# Physoon.net
KiCad netlist of a schematic drawn in EAGLE
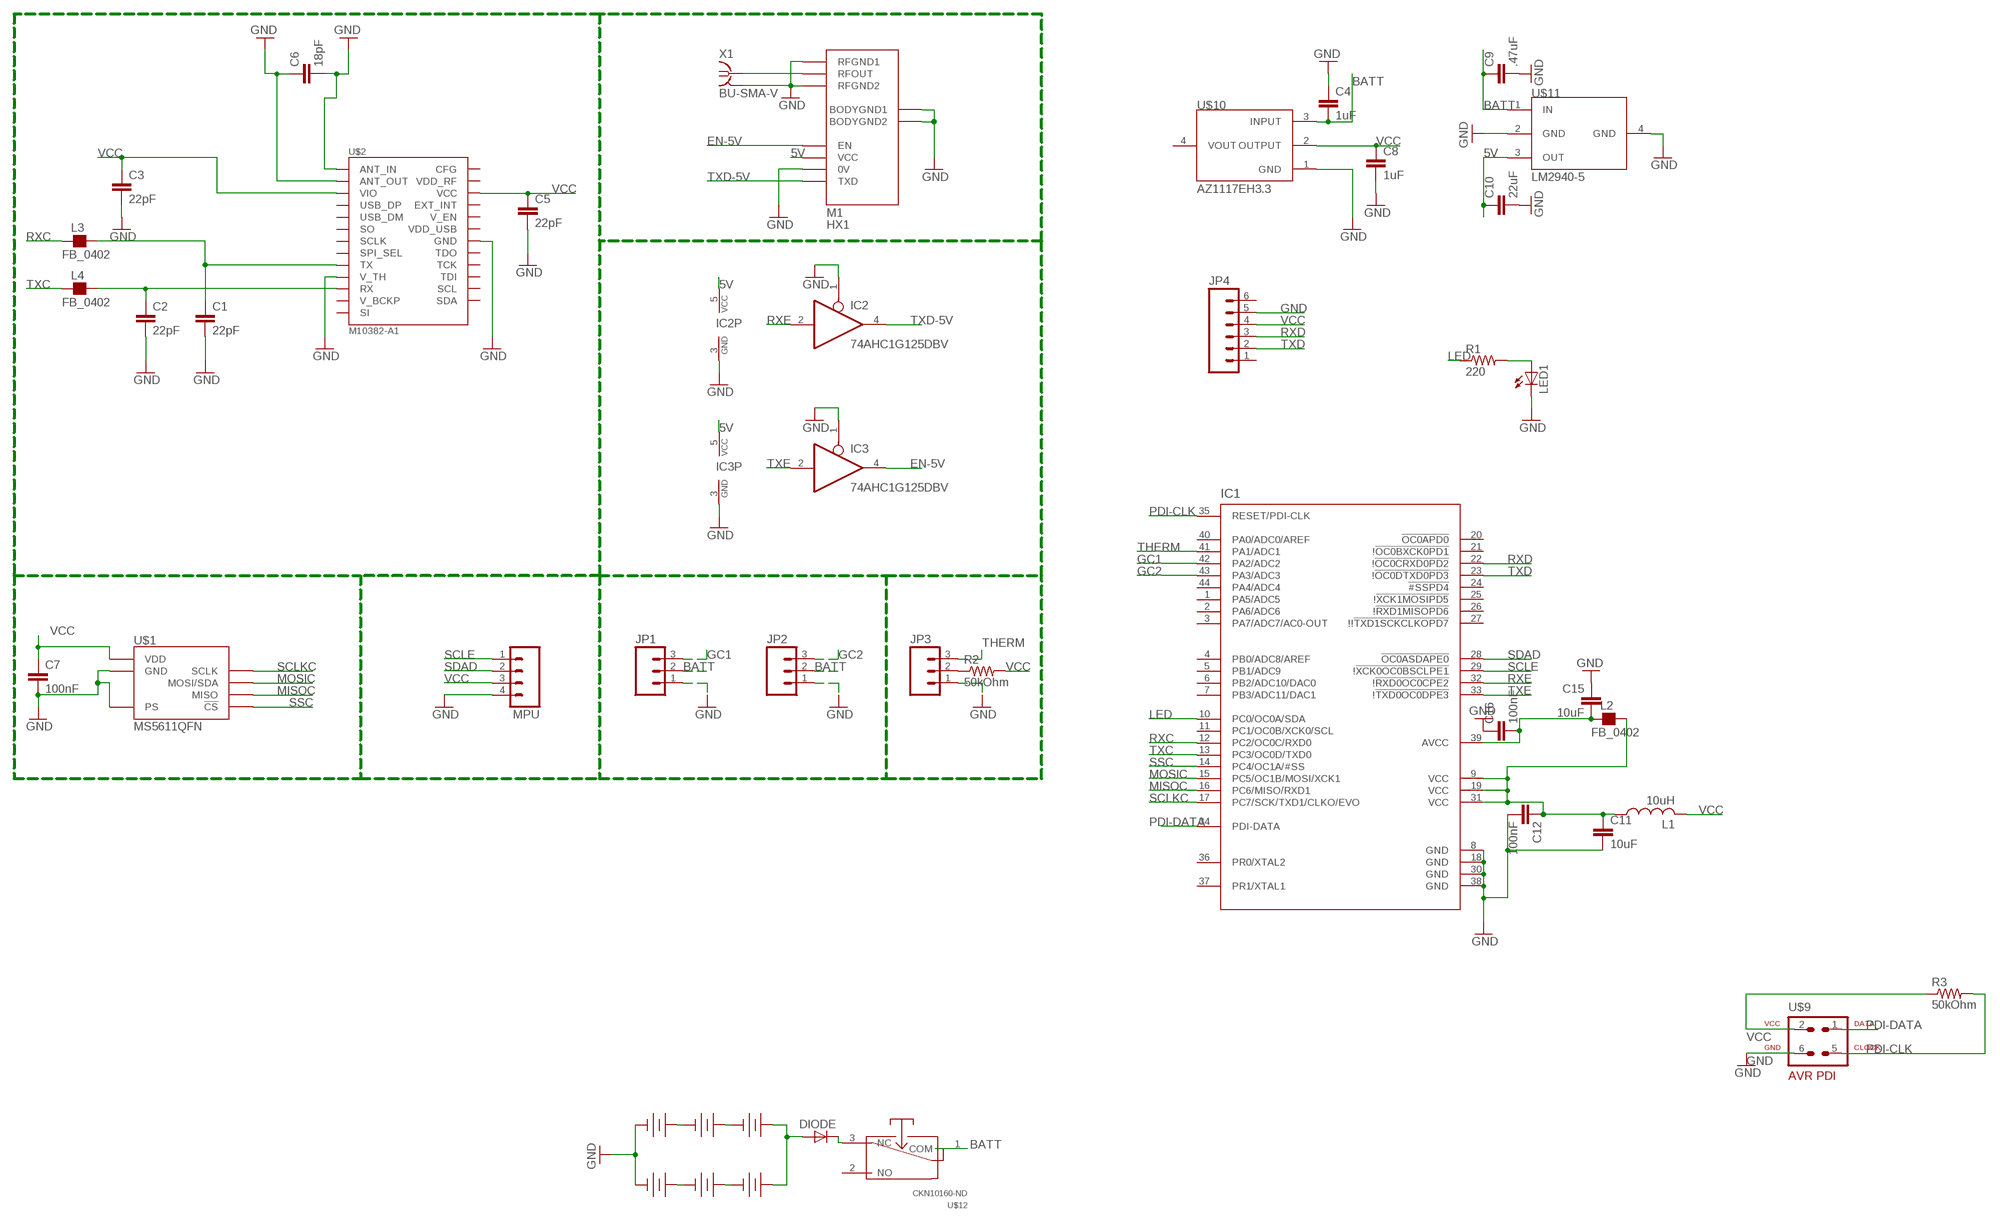
[diagram p0: schematic, sheet 1]

(export (version "E")
  (design (tool "Eeschema 10.0.6"))
  (components
    (comp (ref "C1")
      (value "22pF")
      (footprint "eagle-import:0805")
      (libsource (lib "eagle-import") (part "CAP0805"))
    )
    (comp (ref "C2")
      (value "22pF")
      (footprint "eagle-import:0805")
      (libsource (lib "eagle-import") (part "CAP0805"))
    )
    (comp (ref "C3")
      (value "22pF")
      (footprint "eagle-import:0805")
      (libsource (lib "eagle-import") (part "CAP0805"))
    )
    (comp (ref "C4")
      (value "1uF")
      (footprint "eagle-import:0603-CAP")
      (libsource (lib "eagle-import") (part "CAP0603-CAP"))
    )
    (comp (ref "C5")
      (value "22pF")
      (footprint "eagle-import:0805")
      (libsource (lib "eagle-import") (part "CAP0805"))
    )
    (comp (ref "C6")
      (value "18pF")
      (footprint "eagle-import:0805")
      (libsource (lib "eagle-import") (part "CAP0805"))
    )
    (comp (ref "C7")
      (value "100nF")
      (footprint "eagle-import:0805")
      (libsource (lib "eagle-import") (part "CAP0805"))
    )
    (comp (ref "C8")
      (value "1uF")
      (footprint "eagle-import:0603-CAP")
      (libsource (lib "eagle-import") (part "CAP0603-CAP"))
    )
    (comp (ref "C9")
      (value ".47uF")
      (footprint "eagle-import:0603-CAP")
      (libsource (lib "eagle-import") (part "CAP0603-CAP"))
    )
    (comp (ref "C10")
      (value "22uF")
      (footprint "eagle-import:0603-CAP")
      (libsource (lib "eagle-import") (part "CAP0603-CAP"))
    )
    (comp (ref "C11")
      (value "10uF")
      (footprint "eagle-import:0805")
      (libsource (lib "eagle-import") (part "CAP0805"))
    )
    (comp (ref "C12")
      (value "100nF")
      (footprint "eagle-import:0805")
      (libsource (lib "eagle-import") (part "CAP0805"))
    )
    (comp (ref "C15")
      (value "10uF")
      (footprint "eagle-import:0805")
      (libsource (lib "eagle-import") (part "CAP0805"))
    )
    (comp (ref "C16")
      (value "100nF")
      (footprint "eagle-import:0805")
      (libsource (lib "eagle-import") (part "CAP0805"))
    )
    (comp (ref "DIODE")
      (value "LILYPAD-WEARABLES_LED1206")
      (footprint "eagle-import:LILYPAD-WEARABLES_LED-1206")
      (libsource (lib "eagle-import") (part "LILYPAD-WEARABLES_LED1206"))
    )
    (comp (ref "IC1")
      (value "AT-XMEGA-XXA4-AU")
      (footprint "eagle-import:QFP80P1200X1200X120-44N")
      (libsource (lib "eagle-import") (part "AT-XMEGA-XXA4-AU"))
    )
    (comp (ref "IC2")
      (value "74AHC1G125DBV")
      (footprint "eagle-import:SOT23-5")
      (libsource (lib "eagle-import") (part "741G125DBVAHC"))
    )
    (comp (ref "IC3")
      (value "74AHC1G125DBV")
      (footprint "eagle-import:SOT23-5")
      (libsource (lib "eagle-import") (part "741G125DBVAHC"))
    )
    (comp (ref "JP1")
      (value "M03JST-PTH")
      (footprint "eagle-import:JST-3-PTH")
      (libsource (lib "eagle-import") (part "M03JST-PTH"))
    )
    (comp (ref "JP2")
      (value "M03JST-PTH")
      (footprint "eagle-import:JST-3-PTH")
      (libsource (lib "eagle-import") (part "M03JST-PTH"))
    )
    (comp (ref "JP3")
      (value "M03JST-PTH")
      (footprint "eagle-import:JST-3-PTH")
      (libsource (lib "eagle-import") (part "M03JST-PTH"))
    )
    (comp (ref "JP4")
      (value "M06POLAR")
      (footprint "eagle-import:MOLEX-1X6")
      (libsource (lib "eagle-import") (part "M06POLAR"))
    )
    (comp (ref "L1")
      (value "10uH")
      (footprint "eagle-import:L2012C")
      (libsource (lib "eagle-import") (part "L-USL2012C"))
    )
    (comp (ref "L2")
      (value "FB_0402")
      (footprint "eagle-import:L0402")
      (libsource (lib "eagle-import") (part "FB_0402"))
    )
    (comp (ref "L3")
      (value "FB_0402")
      (footprint "eagle-import:L0402")
      (libsource (lib "eagle-import") (part "FB_0402"))
    )
    (comp (ref "L4")
      (value "FB_0402")
      (footprint "eagle-import:L0402")
      (libsource (lib "eagle-import") (part "FB_0402"))
    )
    (comp (ref "LED1")
      (value "LEDCHIP-LED0603")
      (footprint "eagle-import:CHIP-LED0603")
      (libsource (lib "eagle-import") (part "LEDCHIP-LED0603"))
    )
    (comp (ref "M1")
      (value "HX1")
      (footprint "eagle-import:HX1")
      (libsource (lib "eagle-import") (part "HX1"))
    )
    (comp (ref "MPU")
      (value "M04")
      (footprint "eagle-import:04P")
      (libsource (lib "eagle-import") (part "M04"))
    )
    (comp (ref "R1")
      (value "220")
      (footprint "eagle-import:R0603")
      (libsource (lib "eagle-import") (part "R-US_R0603"))
    )
    (comp (ref "R2")
      (value "50kOhm")
      (footprint "eagle-import:0805")
      (libsource (lib "eagle-import") (part "RESISTOR0805-RES"))
    )
    (comp (ref "R3")
      (value "50kOhm")
      (footprint "eagle-import:0805")
      (libsource (lib "eagle-import") (part "RESISTOR0805-RES"))
    )
    (comp (ref "U$1")
      (value "MS5611QFN")
      (footprint "eagle-import:MS5611-01BA01")
      (libsource (lib "eagle-import") (part "MS5611QFN"))
    )
    (comp (ref "U$2")
      (value "M10382-A1")
      (footprint "eagle-import:M10382-A1")
      (libsource (lib "eagle-import") (part "M10382-A1"))
    )
    (comp (ref "U$3")
      (value "123_BATTERY_HOLDERCR-123-A")
      (footprint "eagle-import:CR-123-A_HOLDER")
      (libsource (lib "eagle-import") (part "123_BATTERY_HOLDERCR-123-A"))
    )
    (comp (ref "U$4")
      (value "123_BATTERY_HOLDERCR-123-A")
      (footprint "eagle-import:CR-123-A_HOLDER")
      (libsource (lib "eagle-import") (part "123_BATTERY_HOLDERCR-123-A"))
    )
    (comp (ref "U$5")
      (value "123_BATTERY_HOLDERCR-123-A")
      (footprint "eagle-import:CR-123-A_HOLDER")
      (libsource (lib "eagle-import") (part "123_BATTERY_HOLDERCR-123-A"))
    )
    (comp (ref "U$6")
      (value "123_BATTERY_HOLDERCR-123-A")
      (footprint "eagle-import:CR-123-A_HOLDER")
      (libsource (lib "eagle-import") (part "123_BATTERY_HOLDERCR-123-A"))
    )
    (comp (ref "U$7")
      (value "123_BATTERY_HOLDERCR-123-A")
      (footprint "eagle-import:CR-123-A_HOLDER")
      (libsource (lib "eagle-import") (part "123_BATTERY_HOLDERCR-123-A"))
    )
    (comp (ref "U$8")
      (value "123_BATTERY_HOLDERCR-123-A")
      (footprint "eagle-import:CR-123-A_HOLDER")
      (libsource (lib "eagle-import") (part "123_BATTERY_HOLDERCR-123-A"))
    )
    (comp (ref "U$9")
      (value "AVR-PDIVERT")
      (footprint "eagle-import:AVR-ISP-6")
      (libsource (lib "eagle-import") (part "AVR-PDIVERT"))
    )
    (comp (ref "U$10")
      (value "AZ1117EH3.3")
      (footprint "eagle-import:SOT-223")
      (libsource (lib "eagle-import") (part "AZ1117EH3.3"))
    )
    (comp (ref "U$11")
      (value "LM2940-5")
      (footprint "eagle-import:SOT-223")
      (libsource (lib "eagle-import") (part "LM2940-5"))
    )
    (comp (ref "U$12")
      (value "CKN10160-ND")
      (footprint "eagle-import:ZMCHFL3R")
      (libsource (lib "eagle-import") (part "CKN10160-ND"))
    )
    (comp (ref "X1")
      (value "BU-SMA-V")
      (footprint "eagle-import:BU-SMA-V")
      (libsource (lib "eagle-import") (part "BU-SMA-V"))
    )
  )
  (nets
    (net (code "1") (name "/5V") (class "Default")
      (node (ref "C10") (pin "1") (pinfunction "1_1") (pintype "passive"))
      (node (ref "IC2") (pin "5") (pinfunction "VCC_5") (pintype "power_in"))
      (node (ref "IC3") (pin "5") (pinfunction "VCC_5") (pintype "power_in"))
      (node (ref "M1") (pin "VCC") (pinfunction "VCC_VCC") (pintype "bidirectional"))
      (node (ref "U$11") (pin "3") (pinfunction "OUT_3") (pintype "bidirectional"))
    )
    (net (code "2") (name "/BATT") (class "Default")
      (node (ref "C4") (pin "2") (pinfunction "2_2") (pintype "passive"))
      (node (ref "C9") (pin "1") (pinfunction "1_1") (pintype "passive"))
      (node (ref "JP1") (pin "2") (pinfunction "2_2") (pintype "passive"))
      (node (ref "JP2") (pin "2") (pinfunction "2_2") (pintype "passive"))
      (node (ref "U$10") (pin "3") (pinfunction "INPUT_3") (pintype "bidirectional"))
      (node (ref "U$11") (pin "1") (pinfunction "IN_1") (pintype "bidirectional"))
      (node (ref "U$12") (pin "1") (pinfunction "COM_1") (pintype "bidirectional"))
    )
    (net (code "3") (name "/EN-5V") (class "Default")
      (node (ref "IC3") (pin "4") (pinfunction "O_4") (pintype "tri_state"))
      (node (ref "M1") (pin "EN") (pinfunction "EN_EN") (pintype "bidirectional"))
    )
    (net (code "4") (name "/GC1") (class "Default")
      (node (ref "IC1") (pin "42") (pinfunction "PA2/ADC2_42") (pintype "bidirectional"))
      (node (ref "JP1") (pin "3") (pinfunction "3_3") (pintype "passive"))
    )
    (net (code "5") (name "/GC2") (class "Default")
      (node (ref "IC1") (pin "43") (pinfunction "PA3/ADC3_43") (pintype "bidirectional"))
      (node (ref "JP2") (pin "3") (pinfunction "3_3") (pintype "passive"))
    )
    (net (code "6") (name "/LED") (class "Default")
      (node (ref "IC1") (pin "10") (pinfunction "PC0/OC0A/SDA_10") (pintype "bidirectional"))
      (node (ref "R1") (pin "1") (pinfunction "1_1") (pintype "passive"))
    )
    (net (code "7") (name "/MISOC") (class "Default")
      (node (ref "IC1") (pin "16") (pinfunction "PC6/MISO/RXD1_16") (pintype "bidirectional"))
      (node (ref "U$1") (pin "6") (pinfunction "MISO_6") (pintype "bidirectional"))
    )
    (net (code "8") (name "/MOSIC") (class "Default")
      (node (ref "IC1") (pin "15") (pinfunction "PC5/OC1B/MOSI/XCK1_15") (pintype "bidirectional"))
      (node (ref "U$1") (pin "7") (pinfunction "MOSI/SDA_7") (pintype "bidirectional"))
    )
    (net (code "9") (name "/PDI-CLK") (class "Default")
      (node (ref "IC1") (pin "35") (pinfunction "RESET/PDI-CLK_35") (pintype "input"))
      (node (ref "R3") (pin "2") (pinfunction "2_2") (pintype "passive"))
      (node (ref "U$9") (pin "5") (pinfunction "5_5") (pintype "passive"))
    )
    (net (code "10") (name "/PDI-DATA") (class "Default")
      (node (ref "IC1") (pin "34") (pinfunction "PDI-DATA_34") (pintype "bidirectional"))
      (node (ref "U$9") (pin "1") (pinfunction "1_1") (pintype "passive"))
    )
    (net (code "11") (name "/RXC") (class "Default")
      (node (ref "IC1") (pin "12") (pinfunction "PC2/OC0C/RXD0_12") (pintype "bidirectional"))
      (node (ref "L3") (pin "1") (pinfunction "1_1") (pintype "passive"))
    )
    (net (code "12") (name "/RXD") (class "Default")
      (node (ref "IC1") (pin "22") (pinfunction "~OC0CRXD0PD2_22") (pintype "bidirectional"))
      (node (ref "JP4") (pin "3") (pinfunction "3_3") (pintype "passive"))
    )
    (net (code "13") (name "/RXE") (class "Default")
      (node (ref "IC1") (pin "32") (pinfunction "~RXD0OC0CPE2_32") (pintype "bidirectional"))
      (node (ref "IC2") (pin "2") (pinfunction "I_2") (pintype "input"))
    )
    (net (code "14") (name "/SCLE") (class "Default")
      (node (ref "IC1") (pin "29") (pinfunction "~XCK0OC0BSCLPE1_29") (pintype "bidirectional"))
      (node (ref "MPU") (pin "1") (pinfunction "1_1") (pintype "passive"))
    )
    (net (code "15") (name "/SCLKC") (class "Default")
      (node (ref "IC1") (pin "17") (pinfunction "PC7/SCK/TXD1/CLKO/EVO_17") (pintype "bidirectional"))
      (node (ref "U$1") (pin "8") (pinfunction "SCLK_8") (pintype "bidirectional"))
    )
    (net (code "16") (name "/SDAD") (class "Default")
      (node (ref "IC1") (pin "28") (pinfunction "~{OC0ASDAPE0}_28") (pintype "bidirectional"))
      (node (ref "MPU") (pin "2") (pinfunction "2_2") (pintype "passive"))
    )
    (net (code "17") (name "/SSC") (class "Default")
      (node (ref "IC1") (pin "14") (pinfunction "PC4/OC1A/#SS_14") (pintype "bidirectional"))
      (node (ref "U$1") (pin "4") (pinfunction "~{CS}_4") (pintype "bidirectional"))
      (node (ref "U$1") (pin "5") (pinfunction "~{CS}_5") (pintype "bidirectional"))
    )
    (net (code "18") (name "/THERM") (class "Default")
      (node (ref "IC1") (pin "41") (pinfunction "PA1/ADC1_41") (pintype "bidirectional"))
      (node (ref "JP3") (pin "3") (pinfunction "3_3") (pintype "passive"))
    )
    (net (code "19") (name "/TXC") (class "Default")
      (node (ref "IC1") (pin "13") (pinfunction "PC3/OC0D/TXD0_13") (pintype "bidirectional"))
      (node (ref "L4") (pin "1") (pinfunction "1_1") (pintype "passive"))
    )
    (net (code "20") (name "/TXD") (class "Default")
      (node (ref "IC1") (pin "23") (pinfunction "~OC0DTXD0PD3_23") (pintype "bidirectional"))
      (node (ref "JP4") (pin "2") (pinfunction "2_2") (pintype "passive"))
    )
    (net (code "21") (name "/TXD-5V") (class "Default")
      (node (ref "IC2") (pin "4") (pinfunction "O_4") (pintype "tri_state"))
      (node (ref "M1") (pin "TXD") (pinfunction "TXD_TXD") (pintype "bidirectional"))
    )
    (net (code "22") (name "/TXE") (class "Default")
      (node (ref "IC1") (pin "33") (pinfunction "~TXD0OC0DPE3_33") (pintype "bidirectional"))
      (node (ref "IC3") (pin "2") (pinfunction "I_2") (pintype "input"))
    )
    (net (code "23") (name "/VCC") (class "Default")
      (node (ref "C3") (pin "1") (pinfunction "1_1") (pintype "passive"))
      (node (ref "C5") (pin "1") (pinfunction "1_1") (pintype "passive"))
      (node (ref "C7") (pin "1") (pinfunction "1_1") (pintype "passive"))
      (node (ref "C8") (pin "1") (pinfunction "1_1") (pintype "passive"))
      (node (ref "JP4") (pin "4") (pinfunction "4_4") (pintype "passive"))
      (node (ref "L1") (pin "2") (pinfunction "2_2") (pintype "passive"))
      (node (ref "MPU") (pin "3") (pinfunction "3_3") (pintype "passive"))
      (node (ref "R2") (pin "2") (pinfunction "2_2") (pintype "passive"))
      (node (ref "R3") (pin "1") (pinfunction "1_1") (pintype "passive"))
      (node (ref "U$1") (pin "1") (pinfunction "VDD_1") (pintype "bidirectional"))
      (node (ref "U$10") (pin "2") (pinfunction "OUTPUT_2") (pintype "bidirectional"))
      (node (ref "U$2") (pin "27") (pinfunction "VCC_27") (pintype "bidirectional"))
      (node (ref "U$2") (pin "5") (pinfunction "VIO_5") (pintype "bidirectional"))
      (node (ref "U$9") (pin "2") (pinfunction "2_2") (pintype "passive"))
    )
    (net (code "24") (name "GND") (class "Default")
      (node (ref "C1") (pin "2") (pinfunction "2_2") (pintype "passive"))
      (node (ref "C10") (pin "2") (pinfunction "2_2") (pintype "passive"))
      (node (ref "C11") (pin "2") (pinfunction "2_2") (pintype "passive"))
      (node (ref "C12") (pin "2") (pinfunction "2_2") (pintype "passive"))
      (node (ref "C15") (pin "1") (pinfunction "1_1") (pintype "passive"))
      (node (ref "C16") (pin "1") (pinfunction "1_1") (pintype "passive"))
      (node (ref "C2") (pin "2") (pinfunction "2_2") (pintype "passive"))
      (node (ref "C3") (pin "2") (pinfunction "2_2") (pintype "passive"))
      (node (ref "C4") (pin "1") (pinfunction "1_1") (pintype "passive"))
      (node (ref "C5") (pin "2") (pinfunction "2_2") (pintype "passive"))
      (node (ref "C6") (pin "1") (pinfunction "1_1") (pintype "passive"))
      (node (ref "C6") (pin "2") (pinfunction "2_2") (pintype "passive"))
      (node (ref "C7") (pin "2") (pinfunction "2_2") (pintype "passive"))
      (node (ref "C8") (pin "2") (pinfunction "2_2") (pintype "passive"))
      (node (ref "C9") (pin "2") (pinfunction "2_2") (pintype "passive"))
      (node (ref "IC1") (pin "18") (pinfunction "GND_18") (pintype "power_in"))
      (node (ref "IC1") (pin "30") (pinfunction "GND_30") (pintype "power_in"))
      (node (ref "IC1") (pin "38") (pinfunction "GND_38") (pintype "power_in"))
      (node (ref "IC1") (pin "8") (pinfunction "GND_8") (pintype "power_in"))
      (node (ref "IC2") (pin "1") (pinfunction "OE_1") (pintype "input"))
      (node (ref "IC2") (pin "3") (pinfunction "GND_3") (pintype "power_in"))
      (node (ref "IC3") (pin "1") (pinfunction "OE_1") (pintype "input"))
      (node (ref "IC3") (pin "3") (pinfunction "GND_3") (pintype "power_in"))
      (node (ref "JP1") (pin "1") (pinfunction "1_1") (pintype "passive"))
      (node (ref "JP2") (pin "1") (pinfunction "1_1") (pintype "passive"))
      (node (ref "JP3") (pin "1") (pinfunction "1_1") (pintype "passive"))
      (node (ref "JP4") (pin "5") (pinfunction "5_5") (pintype "passive"))
      (node (ref "LED1") (pin "C") (pinfunction "C_C") (pintype "passive"))
      (node (ref "M1") (pin "0V") (pinfunction "0V_0V") (pintype "bidirectional"))
      (node (ref "M1") (pin "BODYGND1") (pinfunction "BODYGND1_BODYGND1") (pintype "bidirectional"))
      (node (ref "M1") (pin "BODYGND2") (pinfunction "BODYGND2_BODYGND2") (pintype "bidirectional"))
      (node (ref "M1") (pin "RFGND1") (pinfunction "RFGND1_RFGND1") (pintype "bidirectional"))
      (node (ref "M1") (pin "RFGND2") (pinfunction "RFGND2_RFGND2") (pintype "bidirectional"))
      (node (ref "MPU") (pin "4") (pinfunction "4_4") (pintype "passive"))
      (node (ref "U$1") (pin "2") (pinfunction "PS_2") (pintype "bidirectional"))
      (node (ref "U$1") (pin "3") (pinfunction "GND_3") (pintype "bidirectional"))
      (node (ref "U$10") (pin "1") (pinfunction "GND_1") (pintype "bidirectional"))
      (node (ref "U$11") (pin "2") (pinfunction "GND_2") (pintype "bidirectional"))
      (node (ref "U$11") (pin "4") (pinfunction "GND_4") (pintype "bidirectional"))
      (node (ref "U$2") (pin "1") (pinfunction "ANT_IN_1") (pintype "bidirectional"))
      (node (ref "U$2") (pin "12") (pinfunction "V_TH_12") (pintype "bidirectional"))
      (node (ref "U$2") (pin "14") (pinfunction "GND_14") (pintype "bidirectional"))
      (node (ref "U$2") (pin "17") (pinfunction "GND_17") (pintype "bidirectional"))
      (node (ref "U$2") (pin "2") (pinfunction "GND_2") (pintype "bidirectional"))
      (node (ref "U$2") (pin "21") (pinfunction "GND_21") (pintype "bidirectional"))
      (node (ref "U$2") (pin "24") (pinfunction "GND_24") (pintype "bidirectional"))
      (node (ref "U$2") (pin "26") (pinfunction "GND_26") (pintype "bidirectional"))
      (node (ref "U$2") (pin "28") (pinfunction "GND_28") (pintype "bidirectional"))
      (node (ref "U$2") (pin "3") (pinfunction "ANT_OUT_3") (pintype "bidirectional"))
      (node (ref "U$2") (pin "33") (pinfunction "GND_33") (pintype "bidirectional"))
      (node (ref "U$2") (pin "34") (pinfunction "GND_34") (pintype "bidirectional"))
      (node (ref "U$2") (pin "35") (pinfunction "GND_35") (pintype "bidirectional"))
      (node (ref "U$2") (pin "36") (pinfunction "GND_36") (pintype "bidirectional"))
      (node (ref "U$2") (pin "4") (pinfunction "GND_4") (pintype "bidirectional"))
      (node (ref "U$3") (pin "-") (pinfunction "-_-") (pintype "bidirectional"))
      (node (ref "U$6") (pin "-") (pinfunction "-_-") (pintype "bidirectional"))
      (node (ref "U$9") (pin "6") (pinfunction "6_6") (pintype "passive"))
      (node (ref "X1") (pin "2") (pinfunction "GND_2") (pintype "power_in"))
    )
    (net (code "25") (name "Net-(C11-Pad1)") (class "Default")
      (node (ref "C11") (pin "1") (pinfunction "1_1") (pintype "passive"))
      (node (ref "C12") (pin "1") (pinfunction "1_1") (pintype "passive"))
      (node (ref "IC1") (pin "19") (pinfunction "VCC_19") (pintype "power_in"))
      (node (ref "IC1") (pin "31") (pinfunction "VCC_31") (pintype "power_in"))
      (node (ref "IC1") (pin "9") (pinfunction "VCC_9") (pintype "power_in"))
      (node (ref "L1") (pin "1") (pinfunction "1_1") (pintype "passive"))
      (node (ref "L2") (pin "2") (pinfunction "2_2") (pintype "passive"))
    )
    (net (code "26") (name "Net-(DIODE-PadA)") (class "Default")
      (node (ref "DIODE") (pin "A") (pinfunction "A_A") (pintype "passive"))
      (node (ref "U$5") (pin "+") (pinfunction "+_+") (pintype "bidirectional"))
      (node (ref "U$8") (pin "+") (pinfunction "+_+") (pintype "bidirectional"))
    )
    (net (code "27") (name "Net-(IC1-AVCC)") (class "Default")
      (node (ref "C15") (pin "2") (pinfunction "2_2") (pintype "passive"))
      (node (ref "C16") (pin "2") (pinfunction "2_2") (pintype "passive"))
      (node (ref "IC1") (pin "39") (pinfunction "AVCC_39") (pintype "power_in"))
      (node (ref "L2") (pin "1") (pinfunction "1_1") (pintype "passive"))
    )
    (net (code "28") (name "Net-(JP3-Pad2)") (class "Default")
      (node (ref "JP3") (pin "2") (pinfunction "2_2") (pintype "passive"))
      (node (ref "R2") (pin "1") (pinfunction "1_1") (pintype "passive"))
    )
    (net (code "29") (name "Net-(LED1-PadA)") (class "Default")
      (node (ref "LED1") (pin "A") (pinfunction "A_A") (pintype "passive"))
      (node (ref "R1") (pin "2") (pinfunction "2_2") (pintype "passive"))
    )
    (net (code "30") (name "Net-(M1-PadRFOUT)") (class "Default")
      (node (ref "M1") (pin "RFOUT") (pinfunction "RFOUT_RFOUT") (pintype "bidirectional"))
      (node (ref "X1") (pin "1") (pinfunction "1_1") (pintype "passive"))
    )
    (net (code "31") (name "Net-(U$2-RX)") (class "Default")
      (node (ref "C2") (pin "1") (pinfunction "1_1") (pintype "passive"))
      (node (ref "L4") (pin "2") (pinfunction "2_2") (pintype "passive"))
      (node (ref "U$2") (pin "13") (pinfunction "RX_13") (pintype "bidirectional"))
    )
    (net (code "32") (name "Net-(U$2-TX)") (class "Default")
      (node (ref "C1") (pin "1") (pinfunction "1_1") (pintype "passive"))
      (node (ref "L3") (pin "2") (pinfunction "2_2") (pintype "passive"))
      (node (ref "U$2") (pin "11") (pinfunction "TX_11") (pintype "bidirectional"))
    )
    (net (code "33") (name "Net-(U$3-Pad+)") (class "Default")
      (node (ref "U$3") (pin "+") (pinfunction "+_+") (pintype "bidirectional"))
      (node (ref "U$4") (pin "-") (pinfunction "-_-") (pintype "bidirectional"))
    )
    (net (code "34") (name "Net-(U$4-Pad+)") (class "Default")
      (node (ref "U$4") (pin "+") (pinfunction "+_+") (pintype "bidirectional"))
      (node (ref "U$5") (pin "-") (pinfunction "-_-") (pintype "bidirectional"))
    )
    (net (code "35") (name "Net-(U$6-Pad+)") (class "Default")
      (node (ref "U$6") (pin "+") (pinfunction "+_+") (pintype "bidirectional"))
      (node (ref "U$7") (pin "-") (pinfunction "-_-") (pintype "bidirectional"))
    )
    (net (code "36") (name "Net-(U$7-Pad+)") (class "Default")
      (node (ref "U$7") (pin "+") (pinfunction "+_+") (pintype "bidirectional"))
      (node (ref "U$8") (pin "-") (pinfunction "-_-") (pintype "bidirectional"))
    )
    (net (code "37") (name "Net-(U$12-NC)") (class "Default")
      (node (ref "DIODE") (pin "C") (pinfunction "C_C") (pintype "passive"))
      (node (ref "U$12") (pin "3") (pinfunction "NC_3") (pintype "bidirectional"))
    )
    (net (code "38") (name "unconnected-(IC1-PA0{slash}ADC0{slash}AREF-Pad40)") (class "Default")
      (node (ref "IC1") (pin "40") (pinfunction "PA0/ADC0/AREF_40") (pintype "bidirectional"))
    )
    (net (code "39") (name "unconnected-(IC1-PA4{slash}ADC4-Pad44)") (class "Default")
      (node (ref "IC1") (pin "44") (pinfunction "PA4/ADC4_44") (pintype "bidirectional"))
    )
    (net (code "40") (name "unconnected-(IC1-PA5{slash}ADC5-Pad1)") (class "Default")
      (node (ref "IC1") (pin "1") (pinfunction "PA5/ADC5_1") (pintype "bidirectional"))
    )
    (net (code "41") (name "unconnected-(IC1-PA6{slash}ADC6-Pad2)") (class "Default")
      (node (ref "IC1") (pin "2") (pinfunction "PA6/ADC6_2") (pintype "bidirectional"))
    )
    (net (code "42") (name "unconnected-(IC1-PA7{slash}ADC7{slash}AC0-OUT-Pad3)") (class "Default")
      (node (ref "IC1") (pin "3") (pinfunction "PA7/ADC7/AC0-OUT_3") (pintype "bidirectional"))
    )
    (net (code "43") (name "unconnected-(IC1-PB0{slash}ADC8{slash}AREF-Pad4)") (class "Default")
      (node (ref "IC1") (pin "4") (pinfunction "PB0/ADC8/AREF_4") (pintype "bidirectional"))
    )
    (net (code "44") (name "unconnected-(IC1-PB1{slash}ADC9-Pad5)") (class "Default")
      (node (ref "IC1") (pin "5") (pinfunction "PB1/ADC9_5") (pintype "bidirectional"))
    )
    (net (code "45") (name "unconnected-(IC1-PB2{slash}ADC10{slash}DAC0-Pad6)") (class "Default")
      (node (ref "IC1") (pin "6") (pinfunction "PB2/ADC10/DAC0_6") (pintype "bidirectional"))
    )
    (net (code "46") (name "unconnected-(IC1-PB3{slash}ADC11{slash}DAC1-Pad7)") (class "Default")
      (node (ref "IC1") (pin "7") (pinfunction "PB3/ADC11/DAC1_7") (pintype "bidirectional"))
    )
    (net (code "47") (name "unconnected-(IC1-PC1{slash}OC0B{slash}XCK0{slash}SCL-Pad11)") (class "Default")
      (node (ref "IC1") (pin "11") (pinfunction "PC1/OC0B/XCK0/SCL_11") (pintype "bidirectional"))
    )
    (net (code "48") (name "unconnected-(IC1-PR0{slash}XTAL2-Pad36)") (class "Default")
      (node (ref "IC1") (pin "36") (pinfunction "PR0/XTAL2_36") (pintype "bidirectional"))
    )
    (net (code "49") (name "unconnected-(IC1-PR1{slash}XTAL1-Pad37)") (class "Default")
      (node (ref "IC1") (pin "37") (pinfunction "PR1/XTAL1_37") (pintype "bidirectional"))
    )
    (net (code "50") (name "unconnected-(IC1-~OC0BXCK0PD1-Pad21)") (class "Default")
      (node (ref "IC1") (pin "21") (pinfunction "~OC0BXCK0PD1_21") (pintype "bidirectional"))
    )
    (net (code "51") (name "unconnected-(IC1-~RXD1MISOPD6-Pad26)") (class "Default")
      (node (ref "IC1") (pin "26") (pinfunction "~RXD1MISOPD6_26") (pintype "bidirectional"))
    )
    (net (code "52") (name "unconnected-(IC1-~XCK1MOSIPD5-Pad25)") (class "Default")
      (node (ref "IC1") (pin "25") (pinfunction "~XCK1MOSIPD5_25") (pintype "bidirectional"))
    )
    (net (code "53") (name "unconnected-(IC1-~{#SSPD4}-Pad24)") (class "Default")
      (node (ref "IC1") (pin "24") (pinfunction "~{#SSPD4}_24") (pintype "bidirectional"))
    )
    (net (code "54") (name "unconnected-(IC1-~{OC0APD0}-Pad20)") (class "Default")
      (node (ref "IC1") (pin "20") (pinfunction "~{OC0APD0}_20") (pintype "bidirectional"))
    )
    (net (code "55") (name "unconnected-(IC1-~~{TXD1SCKCLKOPD7}-Pad27)") (class "Default")
      (node (ref "IC1") (pin "27") (pinfunction "~~{TXD1SCKCLKOPD7}_27") (pintype "bidirectional"))
    )
    (net (code "56") (name "unconnected-(JP4-Pad1)") (class "Default")
      (node (ref "JP4") (pin "1") (pinfunction "1_1") (pintype "passive"))
    )
    (net (code "57") (name "unconnected-(JP4-Pad6)") (class "Default")
      (node (ref "JP4") (pin "6") (pinfunction "6_6") (pintype "passive"))
    )
    (net (code "58") (name "unconnected-(U$2-CFG-Pad31)") (class "Default")
      (node (ref "U$2") (pin "31") (pinfunction "CFG_31") (pintype "bidirectional"))
    )
    (net (code "59") (name "unconnected-(U$2-EXT_INT-Pad29)") (class "Default")
      (node (ref "U$2") (pin "29") (pinfunction "EXT_INT_29") (pintype "bidirectional"))
    )
    (net (code "60") (name "unconnected-(U$2-SCL-Pad19)") (class "Default")
      (node (ref "U$2") (pin "19") (pinfunction "SCL_19") (pintype "bidirectional"))
    )
    (net (code "61") (name "unconnected-(U$2-SCLK-Pad9)") (class "Default")
      (node (ref "U$2") (pin "9") (pinfunction "SCLK_9") (pintype "bidirectional"))
    )
    (net (code "62") (name "unconnected-(U$2-SDA-Pad18)") (class "Default")
      (node (ref "U$2") (pin "18") (pinfunction "SDA_18") (pintype "bidirectional"))
    )
    (net (code "63") (name "unconnected-(U$2-SI-Pad16)") (class "Default")
      (node (ref "U$2") (pin "16") (pinfunction "SI_16") (pintype "bidirectional"))
    )
    (net (code "64") (name "unconnected-(U$2-SO-Pad8)") (class "Default")
      (node (ref "U$2") (pin "8") (pinfunction "SO_8") (pintype "bidirectional"))
    )
    (net (code "65") (name "unconnected-(U$2-SPI_SEL-Pad10)") (class "Default")
      (node (ref "U$2") (pin "10") (pinfunction "SPI_SEL_10") (pintype "bidirectional"))
    )
    (net (code "66") (name "unconnected-(U$2-TCK-Pad22)") (class "Default")
      (node (ref "U$2") (pin "22") (pinfunction "TCK_22") (pintype "bidirectional"))
    )
    (net (code "67") (name "unconnected-(U$2-TDI-Pad20)") (class "Default")
      (node (ref "U$2") (pin "20") (pinfunction "TDI_20") (pintype "bidirectional"))
    )
    (net (code "68") (name "unconnected-(U$2-TDO-Pad23)") (class "Default")
      (node (ref "U$2") (pin "23") (pinfunction "TDO_23") (pintype "bidirectional"))
    )
    (net (code "69") (name "unconnected-(U$2-USB_DM-Pad7)") (class "Default")
      (node (ref "U$2") (pin "7") (pinfunction "USB_DM_7") (pintype "bidirectional"))
    )
    (net (code "70") (name "unconnected-(U$2-USB_DP-Pad6)") (class "Default")
      (node (ref "U$2") (pin "6") (pinfunction "USB_DP_6") (pintype "bidirectional"))
    )
    (net (code "71") (name "unconnected-(U$2-VDD_RF-Pad25)") (class "Default")
      (node (ref "U$2") (pin "25") (pinfunction "VDD_RF_25") (pintype "bidirectional"))
    )
    (net (code "72") (name "unconnected-(U$2-VDD_USB-Pad32)") (class "Default")
      (node (ref "U$2") (pin "32") (pinfunction "VDD_USB_32") (pintype "bidirectional"))
    )
    (net (code "73") (name "unconnected-(U$2-V_BCKP-Pad15)") (class "Default")
      (node (ref "U$2") (pin "15") (pinfunction "V_BCKP_15") (pintype "bidirectional"))
    )
    (net (code "74") (name "unconnected-(U$2-V_EN-Pad30)") (class "Default")
      (node (ref "U$2") (pin "30") (pinfunction "V_EN_30") (pintype "bidirectional"))
    )
    (net (code "75") (name "unconnected-(U$10-VOUT-Pad4)") (class "Default")
      (node (ref "U$10") (pin "4") (pinfunction "VOUT_4") (pintype "bidirectional"))
    )
    (net (code "76") (name "unconnected-(U$12-NO-Pad2)") (class "Default")
      (node (ref "U$12") (pin "2") (pinfunction "NO_2") (pintype "bidirectional"))
    )
  )
)
